# RFID_transmitter_V2.net
KiCad netlist of a schematic drawn in Altium Designer
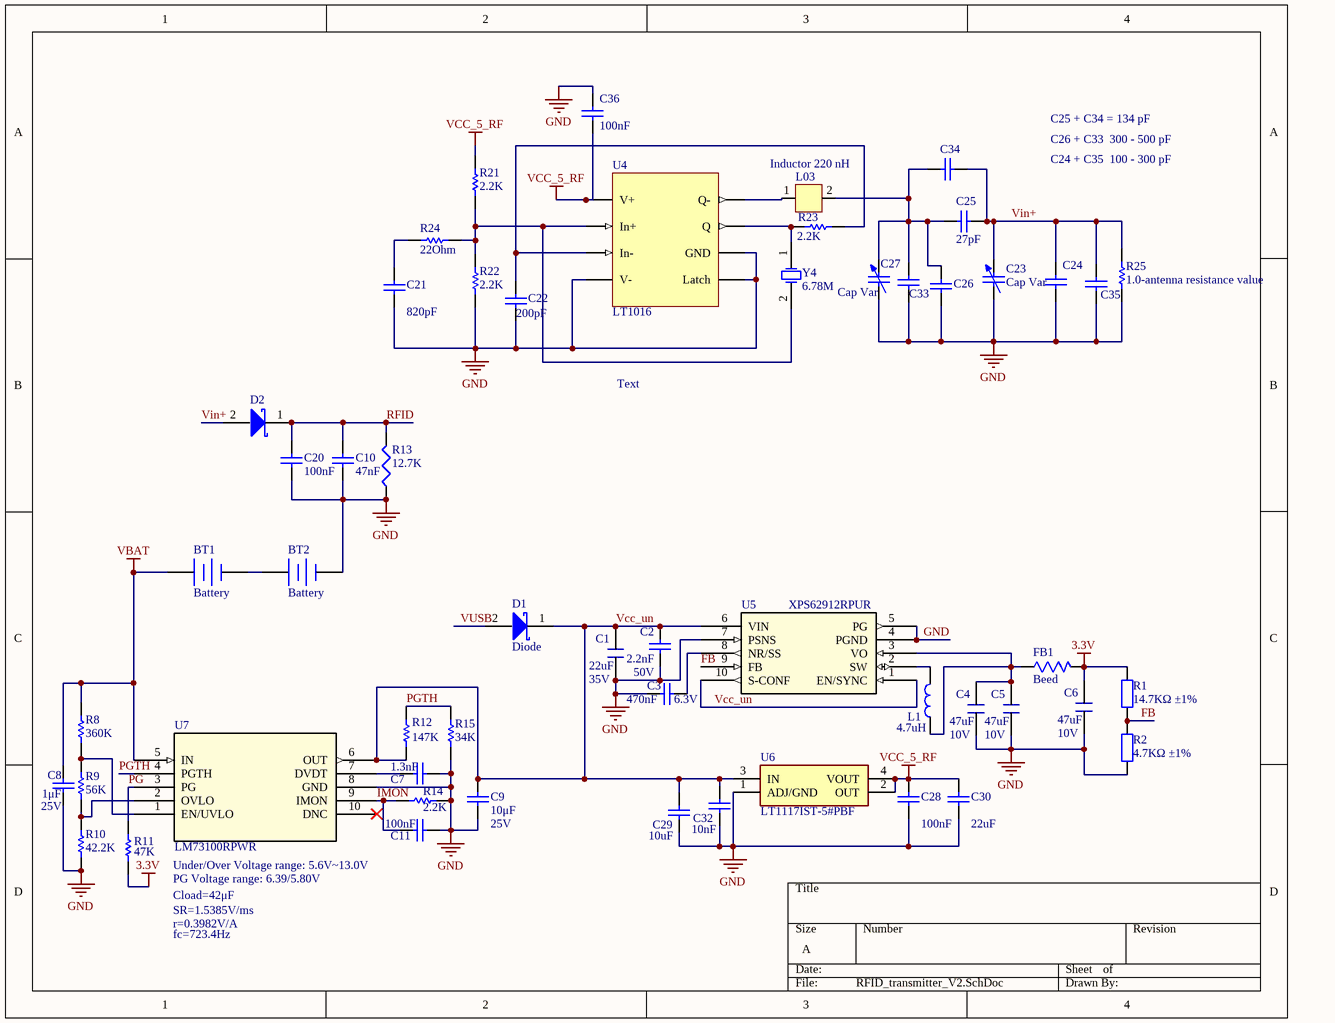
[diagram p0: RFID_transmitter_V2.SchDoc]

(export (version "E")
  (design (tool "Eeschema 10.0.6"))
  (components
    (comp (ref "BT1")
      (value "Battery")
      (footprint "Battery")
      (description "Multicell Battery")
      (fields (field (name "PUBLISHER") "Altium Limited"))
      (libsource (lib "Miscellaneous Devices") (part "Battery"))
    )
    (comp (ref "BT2")
      (value "Battery")
      (footprint "Battery")
      (description "Multicell Battery")
      (fields (field (name "PUBLISHER") "Altium Limited"))
      (libsource (lib "Miscellaneous Devices") (part "Battery"))
    )
    (comp (ref "C1")
      (value "22uF")
      (footprint "C0805")
      (fields
        (field (name "VOLTAGE") "35V")
        (field (name "PART NUMBER") "C2012X5R1V226M125AC")
        (field (name "MANUFACTURER") "TDK")
        (field (name "Comment") "Multilayer Ceramic Capacitor")
      )
      (libsource (lib "Integrated_Library") (part "C-Ceramic"))
    )
    (comp (ref "C2")
      (value "2.2nF")
      (footprint "0402")
      (description "Capacitor (Semiconductor SIM Model)")
      (fields
        (field (name "VOLTAGE") "50V")
        (field (name "PART NUMBER") "GRM155R71H222KA01D")
        (field (name "MANUFACTURER") "MuRata")
        (field (name "PUBLISHER") "Altium Limited")
      )
      (libsource (lib "Miscellaneous Devices") (part "Cap Semi"))
    )
    (comp (ref "C3")
      (value "470nF")
      (footprint "1608[0603]")
      (description "Capacitor (Semiconductor SIM Model)")
      (fields
        (field (name "VOLTAGE") "6.3V")
        (field (name "MANUFACTURER") "MuRata")
        (field (name "PART NUMBER") "GRM188R60J474KA01D")
        (field (name "PUBLISHER") "Altium Limited")
      )
      (libsource (lib "Miscellaneous Devices") (part "Cap Semi"))
    )
    (comp (ref "C4")
      (value "47uF")
      (footprint "C0805")
      (fields
        (field (name "VOLTAGE") "10V")
        (field (name "PART NUMBER") "C2012X5R1A476M125AC")
        (field (name "MANUFACTURER") "TDK")
        (field (name "Comment") "Multilayer Ceramic Capacitor")
      )
      (libsource (lib "Integrated_Library") (part "C-Ceramic"))
    )
    (comp (ref "C5")
      (value "47uF")
      (footprint "C0805")
      (fields
        (field (name "VOLTAGE") "10V")
        (field (name "PART NUMBER") "C2012X5R1A476M125AC")
        (field (name "MANUFACTURER") "TDK")
        (field (name "Comment") "Multilayer Ceramic Capacitor")
      )
      (libsource (lib "Integrated_Library") (part "C-Ceramic"))
    )
    (comp (ref "C6")
      (value "47uF")
      (footprint "C0805")
      (fields
        (field (name "VOLTAGE") "10V")
        (field (name "PART NUMBER") "C2012X5R1A476M125AC")
        (field (name "MANUFACTURER") "TDK")
        (field (name "Comment") "Multilayer Ceramic Capacitor")
      )
      (libsource (lib "Integrated_Library") (part "C-Ceramic"))
    )
    (comp (ref "C7")
      (value "1.3nF")
      (footprint "0402")
      (description "多层陶瓷电容器MLCC - SMD/SMT 1.3nF 50VDC X7R 5% 0402")
      (fields
        (field (name "VOLTAGE") "50V")
        (field (name "PART NUMBER") "GRM155R71H132JA01D")
        (field (name "PUBLISHER") "Altium Limited")
      )
      (libsource (lib "Miscellaneous Devices") (part "Cap Semi"))
    )
    (comp (ref "C8")
      (value "1μF")
      (footprint "1608[0603]")
      (description "多层陶瓷电容器MLCC - SMD/SMT 0603 1uF 25V X6S 10%")
      (fields
        (field (name "VOLTAGE") "25V")
        (field (name "MANUFACTURER") "MuRata")
        (field (name "PART NUMBER") "GRM188C81E105KAADD")
        (field (name "PUBLISHER") "Altium Limited")
      )
      (libsource (lib "Miscellaneous Devices") (part "Cap Semi"))
    )
    (comp (ref "C9")
      (value "10μF")
      (footprint "1608[0603]")
      (description "Capacitor (Semiconductor SIM Model)")
      (fields
        (field (name "VOLTAGE") "25V")
        (field (name "MANUFACTURER") "MuRata")
        (field (name "PART NUMBER") "GRM188R61E106KA73D")
        (field (name "PUBLISHER") "Altium Limited")
      )
      (libsource (lib "Miscellaneous Devices") (part "Cap Semi"))
    )
    (comp (ref "C10")
      (value "47nF")
      (footprint "1608[0603]")
      (description "Capacitor")
      (fields
        (field (name "VOLTAGE") "50V")
        (field (name "PART NUMBER") "CL10B473KB8NNNC")
        (field (name "PUBLISHER") "Altium Limited")
      )
      (libsource (lib "Miscellaneous Devices") (part "Cap Semi"))
    )
    (comp (ref "C11")
      (value "100nF")
      (footprint "0402")
      (description "多层陶瓷电容器MLCC - SMD/SMT 100nF 10VDC X5R 5% 0402")
      (fields
        (field (name "VOLTAGE") "10V")
        (field (name "PART NUMBER") "GRM155R61A104JA01D")
        (field (name "PUBLISHER") "Altium Limited")
      )
      (libsource (lib "Miscellaneous Devices") (part "Cap Semi"))
    )
    (comp (ref "C20")
      (value "100nF")
      (footprint "1608[0603]")
      (description "Capacitor")
      (fields
        (field (name "VOLTAGE") "50V")
        (field (name "PART NUMBER") "CL10B104KB8NNNC")
        (field (name "PUBLISHER") "Altium Limited")
      )
      (libsource (lib "Miscellaneous Devices") (part "Cap Semi"))
    )
    (comp (ref "C21")
      (value "820pF")
      (footprint "0603")
      (description "Capacitor")
      (fields (field (name "Comment") "Cap 820p") (field (name "PUBLISHER") "Altium Limited"))
      (libsource (lib "Miscellaneous Devices") (part "Cap"))
    )
    (comp (ref "C22")
      (value "200pF")
      (footprint "0603")
      (description "Capacitor")
      (fields (field (name "Comment") "Cap 200p") (field (name "PUBLISHER") "Altium Limited"))
      (libsource (lib "Miscellaneous Devices") (part "Cap"))
    )
    (comp (ref "C23")
      (value "Cap Var")
      (footprint "Variable_Capacitor_JZ400HV1")
      (description "Variable or Adjustable Capacitor")
      (fields (field (name "PUBLISHER") "Altium Limited"))
      (libsource (lib "Miscellaneous Devices") (part "Cap Var"))
    )
    (comp (ref "C24")
      (value "Cap")
      (footprint "0603")
      (description "Capacitor_for resonance")
      (fields (field (name "PUBLISHER") "Altium Limited"))
      (libsource (lib "Miscellaneous Devices") (part "Cap"))
    )
    (comp (ref "C25")
      (value "27pF")
      (footprint "0603")
      (description "Capacitor_for resonance")
      (fields (field (name "Comment") "Cap") (field (name "PUBLISHER") "Altium Limited"))
      (libsource (lib "Miscellaneous Devices") (part "Cap"))
    )
    (comp (ref "C26")
      (value "random value needs carefully address")
      (footprint "0603")
      (description "Capacitor_for resonance")
      (fields (field (name "PUBLISHER") "Altium Limited"))
      (libsource (lib "Miscellaneous Devices") (part "Cap"))
    )
    (comp (ref "C27")
      (value "Cap Var")
      (footprint "Variable_Capacitor_JZ400HV1")
      (description "Variable or Adjustable Capacitor")
      (fields (field (name "PUBLISHER") "Altium Limited"))
      (libsource (lib "Miscellaneous Devices") (part "Cap Var"))
    )
    (comp (ref "C28")
      (value "100nF")
      (footprint "0603")
      (description "Capacitor")
      (fields (field (name "Comment") "Cap 100n") (field (name "PUBLISHER") "Altium Limited"))
      (libsource (lib "Miscellaneous Devices") (part "Cap"))
    )
    (comp (ref "C29")
      (value "10uF")
      (footprint "0603")
      (description "Capacitor")
      (fields
        (field (name "PART NUMBER") "GRM188R61E106KA73D")
        (field (name "MANUFACTURER") "Murata")
        (field (name "PUBLISHER") "Altium Limited")
      )
      (libsource (lib "Miscellaneous Devices") (part "Cap"))
    )
    (comp (ref "C30")
      (value "22uF")
      (footprint "0603")
      (description "Capacitor")
      (fields (field (name "Comment") "Cap 22u") (field (name "PUBLISHER") "Altium Limited"))
      (libsource (lib "Miscellaneous Devices") (part "Cap"))
    )
    (comp (ref "C32")
      (value "10nF")
      (footprint "0603")
      (description "Capacitor")
      (fields (field (name "Comment") "Cap 10n") (field (name "PUBLISHER") "Altium Limited"))
      (libsource (lib "Miscellaneous Devices") (part "Cap"))
    )
    (comp (ref "C33")
      (value "random value needs carefully address")
      (footprint "0603")
      (description "Capacitor_for resonance")
      (fields (field (name "PUBLISHER") "Altium Limited"))
      (libsource (lib "Miscellaneous Devices") (part "Cap"))
    )
    (comp (ref "C34")
      (value "Cap")
      (footprint "0603")
      (description "Capacitor_for resonance")
      (fields (field (name "PUBLISHER") "Altium Limited"))
      (libsource (lib "Miscellaneous Devices") (part "Cap"))
    )
    (comp (ref "C35")
      (value "Cap")
      (footprint "0603")
      (description "Capacitor_for resonance")
      (fields (field (name "PUBLISHER") "Altium Limited"))
      (libsource (lib "Miscellaneous Devices") (part "Cap"))
    )
    (comp (ref "C36")
      (value "100nF")
      (footprint "C1210")
      (description "Capacitor (Semiconductor SIM Model)")
      (fields
        (field (name "VOLTAGE") "10V")
        (field (name "PART NUMBER") "C3225C0G1H104JT000N")
        (field (name "PUBLISHER") "Altium Limited")
      )
      (libsource (lib "Miscellaneous Devices") (part "Cap Semi"))
    )
    (comp (ref "D1")
      (value "Diode")
      (footprint "SamacSys:SODFL3616X98N")
      (description "Schottky Power Rectifier, Surface Mount")
      (fields
        (field (name "MANUFACTURER_PART_NUMBER") "MBR120VLSFT1G")
        (field (name "MOUSER PART NUMBER") "863-MBR120VLSFT1G")
      )
      (libsource (lib "SamacSys") (part "MBR120VLSFT1G"))
    )
    (comp (ref "D2")
      (value "Diode")
      (footprint "SamacSys:SOD3716X135N")
      (description "Surface Mount Schottky Power Rectifier")
      (fields
        (field (name "MANUFACTURER_PART_NUMBER") "MBR0540T1G")
        (field (name "MOUSER PART NUMBER") "863-MBR0540T1G")
      )
      (libsource (lib "SamacSys") (part "MBR0540T1G"))
    )
    (comp (ref "FB1")
      (value "Beed")
      (footprint "SamacSys:BEADC2012X110N")
      (description "Wurth Ferrite Bead")
      (fields (field (name "MANUFACTURER_PART_NUMBER") "782853200"))
      (libsource (lib "SamacSys") (part "782853200"))
    )
    (comp (ref "L1")
      (value "4.7uH")
      (footprint "XGL4030")
      (description "Coilcraft Shielded Power Inductors")
      (fields (field (name "PART NUMBER") "XGL4030-472MEC") (field (name "MANUFACTURER") "Coilcraft"))
      (libsource (lib "Integrated_Library") (part "Inductor"))
    )
    (comp (ref "L03")
      (value "Inductor 220 nH")
      (footprint "Ferrite_bead_0805inch_2012mm")
      (description "220nH")
      (libsource (lib "ferrite_bead") (part "Component_1"))
    )
    (comp (ref "R1")
      (value "14.7KΩ ±1%")
      (footprint "LC-0402_R")
      (description "贴片电阻")
      (fields (field (name "PART NUMBER") "CRCW040214K7FKED") (field (name "MANUFACTURER") "Vishay-Dale"))
      (libsource (lib "Miscellaneous Devices LC") (part "0402 1KΩ (1001) 1%"))
    )
    (comp (ref "R2")
      (value "4.7KΩ ±1%")
      (footprint "LC-0402_R")
      (description "贴片电阻")
      (fields (field (name "PART NUMBER") "CRCW04024K70FKED"))
      (libsource (lib "Miscellaneous Devices LC") (part "0402 1KΩ (1001) 1%"))
    )
    (comp (ref "R8")
      (value "360K")
      (footprint "0402-A")
      (description "Resistor")
      (fields
        (field (name "PART NUMBER") "RC0402FR-07360KL")
        (field (name "MANUFACTURER") "YAGEO")
        (field (name "PUBLISHER") "Altium Limited")
      )
      (libsource (lib "Miscellaneous Devices") (part "Res1"))
    )
    (comp (ref "R9")
      (value "56K")
      (footprint "0402-A")
      (description "Resistor")
      (fields
        (field (name "PART NUMBER") "RC0402FR-0756KL")
        (field (name "MANUFACTURER") "YAGEO")
        (field (name "PUBLISHER") "Altium Limited")
      )
      (libsource (lib "Miscellaneous Devices") (part "Res1"))
    )
    (comp (ref "R10")
      (value "42.2K")
      (footprint "0402-A")
      (description "Resistor")
      (fields
        (field (name "PART NUMBER") "RC0603FR-072K2L")
        (field (name "MANUFACTURER") "YAGEO")
        (field (name "PUBLISHER") "Altium Limited")
      )
      (libsource (lib "Miscellaneous Devices") (part "Res1"))
    )
    (comp (ref "R11")
      (value "47K")
      (footprint "0402-A")
      (description "Resistor")
      (fields
        (field (name "PART NUMBER") "RC0402FR-0747KL")
        (field (name "MANUFACTURER") "YAGEO")
        (field (name "PUBLISHER") "Altium Limited")
      )
      (libsource (lib "Miscellaneous Devices") (part "Res1"))
    )
    (comp (ref "R12")
      (value "147K")
      (footprint "0402-A")
      (description "Resistor")
      (fields
        (field (name "PART NUMBER") "RC0402FR-07147KL")
        (field (name "MANUFACTURER") "YAGEO")
        (field (name "PUBLISHER") "Altium Limited")
      )
      (libsource (lib "Miscellaneous Devices") (part "Res1"))
    )
    (comp (ref "R13")
      (value "12.7K")
      (footprint "J1-0603")
      (description "Resistor")
      (fields
        (field (name "PART NUMBER") "RC0603FR-0712K7L")
        (field (name "MANUFACTURER") "YAGEO")
        (field (name "PUBLISHER") "Altium Limited")
      )
      (libsource (lib "Miscellaneous Devices") (part "Res3"))
    )
    (comp (ref "R14")
      (value "2.2K")
      (footprint "0402-A")
      (description "Resistor")
      (fields
        (field (name "PART NUMBER") "RC0402FR-072K2L")
        (field (name "MANUFACTURER") "YAGEO")
        (field (name "PUBLISHER") "Altium Limited")
      )
      (libsource (lib "Miscellaneous Devices") (part "Res1"))
    )
    (comp (ref "R15")
      (value "34K")
      (footprint "0402-A")
      (description "Resistor")
      (fields
        (field (name "PART NUMBER") "RC0402FR-0734KL")
        (field (name "MANUFACTURER") "YAGEO")
        (field (name "PUBLISHER") "Altium Limited")
      )
      (libsource (lib "Miscellaneous Devices") (part "Res1"))
    )
    (comp (ref "R21")
      (value "2.2K")
      (footprint "J1-0603")
      (description "Resistor")
      (fields
        (field (name "PART NUMBER") "RC0603FR-072K2L")
        (field (name "MANUFACTURER") "YAGEO")
        (field (name "PUBLISHER") "Altium Limited")
      )
      (libsource (lib "Miscellaneous Devices") (part "Res1"))
    )
    (comp (ref "R22")
      (value "2.2K")
      (footprint "J1-0603")
      (description "Resistor")
      (fields
        (field (name "PART NUMBER") "RC0603FR-072K2L")
        (field (name "MANUFACTURER") "YAGEO")
        (field (name "PUBLISHER") "Altium Limited")
      )
      (libsource (lib "Miscellaneous Devices") (part "Res1"))
    )
    (comp (ref "R23")
      (value "2.2K")
      (footprint "J1-0603")
      (description "Resistor")
      (fields
        (field (name "PART NUMBER") "RC0603FR-072K2L")
        (field (name "MANUFACTURER") "YAGEO")
        (field (name "PUBLISHER") "Altium Limited")
      )
      (libsource (lib "Miscellaneous Devices") (part "Res1"))
    )
    (comp (ref "R24")
      (value "22Ohm")
      (footprint "J1-0603")
      (description "Resistor")
      (fields
        (field (name "PART NUMBER") "RC0603FR-0722RL")
        (field (name "MANUFACTURER") "YAGEO")
        (field (name "PUBLISHER") "Altium Limited")
      )
      (libsource (lib "Miscellaneous Devices") (part "Res1"))
    )
    (comp (ref "R25")
      (value "1.0-antenna resistance value")
      (footprint "J1-0603")
      (description "Resistor")
      (fields
        (field (name "PART NUMBER") "RC0603FR-071RL")
        (field (name "MANUFACTURER") "YAGEO")
        (field (name "PUBLISHER") "Altium Limited")
      )
      (libsource (lib "Miscellaneous Devices") (part "Res1"))
    )
    (comp (ref "U4") (value "LT1016") (footprint "LT1016_SOIC") (libsource (lib "LT1016") (part "LT1016")))
    (comp (ref "U5")
      (value "XPS62912RPUR")
      (footprint "VQFN-HR10_RPU_TEX")
      (description "No Description Available")
      (fields (field (name "COPYRIGHT") "Copyright (C) 2018 Accelerated Designs. All rights reserved"))
      (libsource (lib "Integrated_Library") (part "XPS62912RPUR"))
    )
    (comp (ref "U6")
      (value "LT1117IST-5#PBF")
      (footprint "SamacSys:SOT230P700X180-4N")
      (libsource (lib "SamacSys") (part "LT1117IST-5#PBF"))
    )
    (comp (ref "U7")
      (value "LM73100RPWR")
      (footprint "VQFN-HR-10_2X2_TEX")
      (description "No Description Available")
      (fields (field (name "COPYRIGHT") "Copyright (C) 2018 Accelerated Designs. All rights reserved"))
      (libsource (lib "Integrated_Library") (part "LM73100RPWR"))
    )
    (comp (ref "Y4")
      (value "CRYSTAL")
      (footprint "HC-49SMD")
      (description "Industry standard SMD crystal")
      (fields
        (field (name "FREQUENCY") "6.78M")
        (field (name "PART NUMBER") "LFXTAL057410Bulk")
        (field (name "MANUFACTURER") "IQD")
      )
      (libsource (lib "Integrated_Library") (part "CRYSTAL"))
    )
  )
  (nets
    (net (code "1") (name "/FB") (class "Default")
      (node (ref "R1") (pin "1") (pinfunction "1_1") (pintype "passive"))
      (node (ref "R2") (pin "2") (pinfunction "2_2") (pintype "passive"))
      (node (ref "U5") (pin "9") (pinfunction "FB_9") (pintype "input"))
    )
    (net (code "2") (name "/IMON") (class "Default")
      (node (ref "C11") (pin "2") (pinfunction "2_2") (pintype "passive"))
      (node (ref "R14") (pin "2") (pinfunction "2_2") (pintype "passive"))
      (node (ref "U7") (pin "9") (pinfunction "IMON_9") (pintype "passive"))
    )
    (net (code "3") (name "/PG") (class "Default")
      (node (ref "R11") (pin "2") (pinfunction "2_2") (pintype "passive"))
      (node (ref "U7") (pin "3") (pinfunction "PG_3") (pintype "passive"))
    )
    (net (code "4") (name "/PGTH") (class "Default")
      (node (ref "R12") (pin "2") (pinfunction "2_2") (pintype "passive"))
      (node (ref "R15") (pin "2") (pinfunction "2_2") (pintype "passive"))
      (node (ref "U7") (pin "4") (pinfunction "PGTH_4") (pintype "passive"))
    )
    (net (code "5") (name "/RFID") (class "Default")
      (node (ref "C10") (pin "1") (pinfunction "1_1") (pintype "passive"))
      (node (ref "C20") (pin "1") (pinfunction "1_1") (pintype "passive"))
      (node (ref "D2") (pin "1") (pinfunction "ANODE_1") (pintype "passive"))
      (node (ref "R13") (pin "2") (pinfunction "2_2") (pintype "passive"))
    )
    (net (code "6") (name "/VUSB") (class "Default")
      (node (ref "D1") (pin "2") (pinfunction "CATHODE_2") (pintype "passive"))
    )
    (net (code "7") (name "/Vcc_un") (class "Default")
      (node (ref "C1") (pin "2") (pinfunction "2_2") (pintype "passive"))
      (node (ref "C2") (pin "2") (pinfunction "2_2") (pintype "passive"))
      (node (ref "C29") (pin "2") (pinfunction "2_2") (pintype "passive"))
      (node (ref "C32") (pin "2") (pinfunction "2_2") (pintype "passive"))
      (node (ref "C9") (pin "2") (pinfunction "2_2") (pintype "passive"))
      (node (ref "D1") (pin "1") (pinfunction "ANODE_1") (pintype "passive"))
      (node (ref "R12") (pin "1") (pinfunction "1_1") (pintype "passive"))
      (node (ref "U5") (pin "1") (pinfunction "EN/SYNC_1") (pintype "input"))
      (node (ref "U5") (pin "10") (pinfunction "S-CONF_10") (pintype "output"))
      (node (ref "U5") (pin "6") (pinfunction "VIN_6") (pintype "power_in"))
      (node (ref "U6") (pin "3") (pinfunction "IN_3") (pintype "passive"))
      (node (ref "U7") (pin "6") (pinfunction "OUT_6") (pintype "output"))
    )
    (net (code "8") (name "/Vin+") (class "Default")
      (node (ref "C23") (pin "2") (pinfunction "2_2") (pintype "passive"))
      (node (ref "C24") (pin "2") (pinfunction "2_2") (pintype "passive"))
      (node (ref "C25") (pin "1") (pinfunction "1_1") (pintype "passive"))
      (node (ref "C34") (pin "1") (pinfunction "1_1") (pintype "passive"))
      (node (ref "C35") (pin "2") (pinfunction "2_2") (pintype "passive"))
      (node (ref "D2") (pin "2") (pinfunction "CATHODE_2") (pintype "passive"))
      (node (ref "R25") (pin "1") (pinfunction "1_1") (pintype "passive"))
    )
    (net (code "9") (name "3.3V") (class "Default")
      (node (ref "C6") (pin "2") (pinfunction "2_2") (pintype "passive"))
      (node (ref "FB1") (pin "2") (pinfunction "2_2") (pintype "passive"))
      (node (ref "R1") (pin "2") (pinfunction "2_2") (pintype "passive"))
      (node (ref "R11") (pin "1") (pinfunction "1_1") (pintype "passive"))
    )
    (net (code "10") (name "GND") (class "Default")
      (node (ref "BT2") (pin "2") (pinfunction "-_2") (pintype "passive"))
      (node (ref "C1") (pin "1") (pinfunction "1_1") (pintype "passive"))
      (node (ref "C10") (pin "2") (pinfunction "2_2") (pintype "passive"))
      (node (ref "C11") (pin "1") (pinfunction "1_1") (pintype "passive"))
      (node (ref "C2") (pin "1") (pinfunction "1_1") (pintype "passive"))
      (node (ref "C20") (pin "2") (pinfunction "2_2") (pintype "passive"))
      (node (ref "C21") (pin "1") (pinfunction "1_1") (pintype "passive"))
      (node (ref "C22") (pin "1") (pinfunction "1_1") (pintype "passive"))
      (node (ref "C23") (pin "1") (pinfunction "1_1") (pintype "passive"))
      (node (ref "C24") (pin "1") (pinfunction "1_1") (pintype "passive"))
      (node (ref "C26") (pin "2") (pinfunction "2_2") (pintype "passive"))
      (node (ref "C27") (pin "1") (pinfunction "1_1") (pintype "passive"))
      (node (ref "C28") (pin "1") (pinfunction "1_1") (pintype "passive"))
      (node (ref "C29") (pin "1") (pinfunction "1_1") (pintype "passive"))
      (node (ref "C3") (pin "1") (pinfunction "1_1") (pintype "passive"))
      (node (ref "C30") (pin "1") (pinfunction "1_1") (pintype "passive"))
      (node (ref "C32") (pin "1") (pinfunction "1_1") (pintype "passive"))
      (node (ref "C33") (pin "2") (pinfunction "2_2") (pintype "passive"))
      (node (ref "C35") (pin "1") (pinfunction "1_1") (pintype "passive"))
      (node (ref "C36") (pin "2") (pinfunction "2_2") (pintype "passive"))
      (node (ref "C4") (pin "1") (pinfunction "1_1") (pintype "passive"))
      (node (ref "C5") (pin "1") (pinfunction "1_1") (pintype "passive"))
      (node (ref "C6") (pin "1") (pinfunction "1_1") (pintype "passive"))
      (node (ref "C7") (pin "1") (pinfunction "1_1") (pintype "passive"))
      (node (ref "C8") (pin "1") (pinfunction "1_1") (pintype "passive"))
      (node (ref "C9") (pin "1") (pinfunction "1_1") (pintype "passive"))
      (node (ref "R10") (pin "1") (pinfunction "1_1") (pintype "passive"))
      (node (ref "R13") (pin "1") (pinfunction "1_1") (pintype "passive"))
      (node (ref "R14") (pin "1") (pinfunction "1_1") (pintype "passive"))
      (node (ref "R15") (pin "1") (pinfunction "1_1") (pintype "passive"))
      (node (ref "R2") (pin "1") (pinfunction "1_1") (pintype "passive"))
      (node (ref "R22") (pin "1") (pinfunction "1_1") (pintype "passive"))
      (node (ref "R25") (pin "2") (pinfunction "2_2") (pintype "passive"))
      (node (ref "U4") (pin "4") (pinfunction "V-_4") (pintype "power_in"))
      (node (ref "U4") (pin "5") (pinfunction "Latch_5") (pintype "passive"))
      (node (ref "U4") (pin "6") (pinfunction "GND_6") (pintype "power_in"))
      (node (ref "U5") (pin "4") (pinfunction "PGND_4") (pintype "passive"))
      (node (ref "U5") (pin "5") (pinfunction "PG_5") (pintype "output"))
      (node (ref "U5") (pin "7") (pinfunction "PSNS_7") (pintype "input"))
      (node (ref "U6") (pin "1") (pinfunction "ADJ/GND_1") (pintype "passive"))
      (node (ref "U7") (pin "8") (pinfunction "GND_8") (pintype "passive"))
    )
    (net (code "11") (name "Net-(BT1--)") (class "Default")
      (node (ref "BT1") (pin "2") (pinfunction "-_2") (pintype "passive"))
      (node (ref "BT2") (pin "1") (pinfunction "+_1") (pintype "passive"))
    )
    (net (code "12") (name "Net-(C21-Pad2)") (class "Default")
      (node (ref "C21") (pin "2") (pinfunction "2_2") (pintype "passive"))
      (node (ref "R24") (pin "2") (pinfunction "2_2") (pintype "passive"))
    )
    (net (code "13") (name "Net-(C25-Pad2)") (class "Default")
      (node (ref "C25") (pin "2") (pinfunction "2_2") (pintype "passive"))
      (node (ref "C26") (pin "1") (pinfunction "1_1") (pintype "passive"))
      (node (ref "C27") (pin "2") (pinfunction "2_2") (pintype "passive"))
      (node (ref "C33") (pin "1") (pinfunction "1_1") (pintype "passive"))
      (node (ref "C34") (pin "2") (pinfunction "2_2") (pintype "passive"))
      (node (ref "L03") (pin "2") (pinfunction "2_2") (pintype "passive"))
    )
    (net (code "14") (name "Net-(U4-In+)") (class "Default")
      (node (ref "R21") (pin "1") (pinfunction "1_1") (pintype "passive"))
      (node (ref "R22") (pin "2") (pinfunction "2_2") (pintype "passive"))
      (node (ref "R24") (pin "1") (pinfunction "1_1") (pintype "passive"))
      (node (ref "U4") (pin "2") (pinfunction "In+_2") (pintype "input"))
      (node (ref "Y4") (pin "2") (pinfunction "OSC2_2") (pintype "passive"))
    )
    (net (code "15") (name "Net-(U4-In-)") (class "Default")
      (node (ref "C22") (pin "2") (pinfunction "2_2") (pintype "passive"))
      (node (ref "R23") (pin "1") (pinfunction "1_1") (pintype "passive"))
      (node (ref "U4") (pin "3") (pinfunction "In-_3") (pintype "input"))
    )
    (net (code "16") (name "Net-(U4-Q)") (class "Default")
      (node (ref "R23") (pin "2") (pinfunction "2_2") (pintype "passive"))
      (node (ref "U4") (pin "7") (pinfunction "Q_7") (pintype "output"))
      (node (ref "Y4") (pin "1") (pinfunction "OSC1_1") (pintype "passive"))
    )
    (net (code "17") (name "Net-(U4-Q-)") (class "Default")
      (node (ref "L03") (pin "1") (pinfunction "1_1") (pintype "passive"))
      (node (ref "U4") (pin "8") (pinfunction "Q-_8") (pintype "output"))
    )
    (net (code "18") (name "Net-(U5-NR{slash}SS)") (class "Default")
      (node (ref "C3") (pin "2") (pinfunction "2_2") (pintype "passive"))
      (node (ref "U5") (pin "8") (pinfunction "NR/SS_8") (pintype "output"))
    )
    (net (code "19") (name "Net-(U5-SW)") (class "Default")
      (node (ref "L1") (pin "2") (pinfunction "2_2") (pintype "passive"))
      (node (ref "U5") (pin "2") (pinfunction "SW_2") (pintype "bidirectional"))
    )
    (net (code "20") (name "Net-(U5-VO)") (class "Default")
      (node (ref "C4") (pin "2") (pinfunction "2_2") (pintype "passive"))
      (node (ref "C5") (pin "2") (pinfunction "2_2") (pintype "passive"))
      (node (ref "FB1") (pin "1") (pinfunction "1_1") (pintype "passive"))
      (node (ref "L1") (pin "1") (pinfunction "1_1") (pintype "passive"))
      (node (ref "U5") (pin "3") (pinfunction "VO_3") (pintype "input"))
    )
    (net (code "21") (name "Net-(U7-DVDT)") (class "Default")
      (node (ref "C7") (pin "2") (pinfunction "2_2") (pintype "passive"))
      (node (ref "U7") (pin "7") (pinfunction "DVDT_7") (pintype "passive"))
    )
    (net (code "22") (name "Net-(U7-EN{slash}UVLO)") (class "Default")
      (node (ref "R8") (pin "1") (pinfunction "1_1") (pintype "passive"))
      (node (ref "R9") (pin "2") (pinfunction "2_2") (pintype "passive"))
      (node (ref "U7") (pin "1") (pinfunction "EN/UVLO_1") (pintype "passive"))
    )
    (net (code "23") (name "Net-(U7-OVLO)") (class "Default")
      (node (ref "R10") (pin "2") (pinfunction "2_2") (pintype "passive"))
      (node (ref "R9") (pin "1") (pinfunction "1_1") (pintype "passive"))
      (node (ref "U7") (pin "2") (pinfunction "OVLO_2") (pintype "passive"))
    )
    (net (code "24") (name "VBAT") (class "Default")
      (node (ref "BT1") (pin "1") (pinfunction "+_1") (pintype "passive"))
      (node (ref "C8") (pin "2") (pinfunction "2_2") (pintype "passive"))
      (node (ref "R8") (pin "2") (pinfunction "2_2") (pintype "passive"))
      (node (ref "U7") (pin "5") (pinfunction "IN_5") (pintype "input"))
    )
    (net (code "25") (name "VCC_5_RF") (class "Default")
      (node (ref "C28") (pin "2") (pinfunction "2_2") (pintype "passive"))
      (node (ref "C30") (pin "2") (pinfunction "2_2") (pintype "passive"))
      (node (ref "C36") (pin "1") (pinfunction "1_1") (pintype "passive"))
      (node (ref "R21") (pin "2") (pinfunction "2_2") (pintype "passive"))
      (node (ref "U4") (pin "1") (pinfunction "V+_1") (pintype "passive"))
      (node (ref "U6") (pin "2") (pinfunction "OUT_2") (pintype "passive"))
      (node (ref "U6") (pin "4") (pinfunction "VOUT_4") (pintype "passive"))
    )
    (net (code "26") (name "unconnected-(U7-DNC-Pad10)") (class "Default")
      (node (ref "U7") (pin "10") (pinfunction "DNC_10") (pintype "passive+no_connect"))
    )
  )
)
